# Obwod_sterowania_MOSFET.net
KiCad netlist of a schematic drawn in Altium Designer
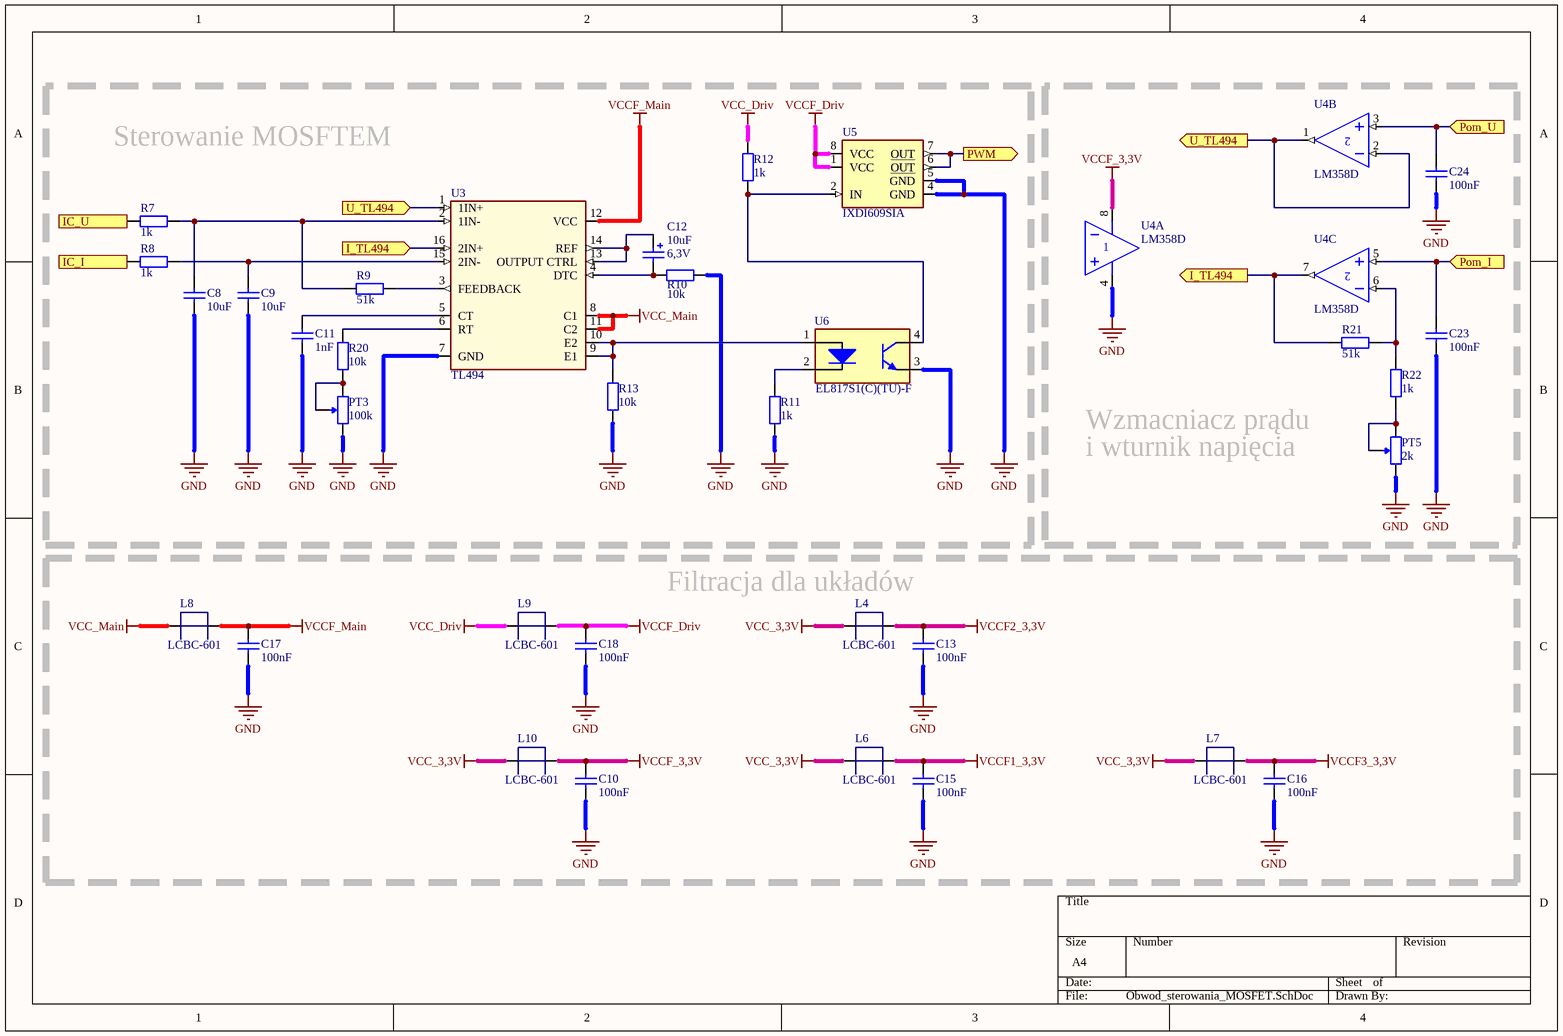
[diagram p0: Obwod_sterowania_MOSFET.SchDoc]

(export (version "E")
  (design (tool "Eeschema 10.0.6"))
  (components
    (comp (ref "C8")
      (value "Kondesator")
      (footprint "SMD-1206C")
      (fields (field (name "PARAMETR_1") "10uF"))
      (libsource (lib "MyLibrary") (part "Kondesator"))
    )
    (comp (ref "C9")
      (value "Kondesator")
      (footprint "SMD-1206C")
      (fields (field (name "PARAMETR_1") "10uF"))
      (libsource (lib "MyLibrary") (part "Kondesator"))
    )
    (comp (ref "C10")
      (value "Kondesator")
      (footprint "SMD-1206C")
      (fields (field (name "PARAMETR_1") "100nF"))
      (libsource (lib "MyLibrary") (part "Kondesator"))
    )
    (comp (ref "C11")
      (value "Kondesator")
      (footprint "SMD-1206C")
      (fields (field (name "PARAMETR_1") "1nF"))
      (libsource (lib "MyLibrary") (part "Kondesator"))
    )
    (comp (ref "C12")
      (value "Kondesator elektrolityczny")
      (footprint "SMD-1206C")
      (fields (field (name "PARAMETR_1") "10uF") (field (name "PARAMETR_2") "6,3V"))
      (libsource (lib "MyLibrary") (part "Kondesator elektrolityczny"))
    )
    (comp (ref "C13")
      (value "Kondesator")
      (footprint "SMD-1206C")
      (fields (field (name "PARAMETR_1") "100nF"))
      (libsource (lib "MyLibrary") (part "Kondesator"))
    )
    (comp (ref "C15")
      (value "Kondesator")
      (footprint "SMD-1206C")
      (fields (field (name "PARAMETR_1") "100nF"))
      (libsource (lib "MyLibrary") (part "Kondesator"))
    )
    (comp (ref "C16")
      (value "Kondesator")
      (footprint "SMD-1206C")
      (fields (field (name "PARAMETR_1") "100nF"))
      (libsource (lib "MyLibrary") (part "Kondesator"))
    )
    (comp (ref "C17")
      (value "Kondesator")
      (footprint "SMD-1206C")
      (fields (field (name "PARAMETR_1") "100nF"))
      (libsource (lib "MyLibrary") (part "Kondesator"))
    )
    (comp (ref "C18")
      (value "Kondesator")
      (footprint "SMD-1206C")
      (fields (field (name "PARAMETR_1") "100nF"))
      (libsource (lib "MyLibrary") (part "Kondesator"))
    )
    (comp (ref "C23")
      (value "Kondesator")
      (footprint "SMD-1206C")
      (fields (field (name "PARAMETR_1") "100nF"))
      (libsource (lib "MyLibrary") (part "Kondesator"))
    )
    (comp (ref "C24")
      (value "Kondesator")
      (footprint "SMD-1206C")
      (fields (field (name "PARAMETR_1") "100nF"))
      (libsource (lib "MyLibrary") (part "Kondesator"))
    )
    (comp (ref "L4")
      (value "~")
      (footprint "SMD-1206-RES")
      (fields (field (name "OZNACZENIE") "LCBC-601"))
      (libsource (lib "MyLibrary") (part "Filtr"))
    )
    (comp (ref "L6")
      (value "~")
      (footprint "SMD-1206-RES")
      (fields (field (name "OZNACZENIE") "LCBC-601"))
      (libsource (lib "MyLibrary") (part "Filtr"))
    )
    (comp (ref "L7")
      (value "~")
      (footprint "SMD-1206-RES")
      (fields (field (name "OZNACZENIE") "LCBC-601"))
      (libsource (lib "MyLibrary") (part "Filtr"))
    )
    (comp (ref "L8")
      (value "~")
      (footprint "SMD-1206-RES")
      (fields (field (name "OZNACZENIE") "LCBC-601"))
      (libsource (lib "MyLibrary") (part "Filtr"))
    )
    (comp (ref "L9")
      (value "~")
      (footprint "SMD-1206-RES")
      (fields (field (name "OZNACZENIE") "LCBC-601"))
      (libsource (lib "MyLibrary") (part "Filtr"))
    )
    (comp (ref "L10")
      (value "~")
      (footprint "SMD-1206-RES")
      (fields (field (name "OZNACZENIE") "LCBC-601"))
      (libsource (lib "MyLibrary") (part "Filtr"))
    )
    (comp (ref "PT3")
      (value "Potentiometer")
      (footprint "Potecjomert")
      (description "Potentiometer montażowy wielobortowy")
      (fields (field (name "PARAMETR_1") "100k"))
      (libsource (lib "MyLibrary") (part "Potentiometer"))
    )
    (comp (ref "PT5")
      (value "Potentiometer")
      (footprint "Potecjomert")
      (description "Potentiometer montażowy wielobortowy")
      (fields (field (name "PARAMETR_1") "2k"))
      (libsource (lib "MyLibrary") (part "Potentiometer"))
    )
    (comp (ref "R7")
      (value "Rezystor")
      (footprint "SMD-1206-RES")
      (fields (field (name "PARAMETR_1") "1k"))
      (libsource (lib "MyLibrary") (part "Rezystor"))
    )
    (comp (ref "R8")
      (value "Rezystor")
      (footprint "SMD-1206-RES")
      (fields (field (name "PARAMETR_1") "1k"))
      (libsource (lib "MyLibrary") (part "Rezystor"))
    )
    (comp (ref "R9")
      (value "Rezystor")
      (footprint "SMD-1206-RES")
      (fields (field (name "PARAMETR_1") "51k"))
      (libsource (lib "") (part "Rezystor_2"))
    )
    (comp (ref "R10")
      (value "Rezystor")
      (footprint "SMD-1206-RES")
      (fields (field (name "PARAMETR_1") "10k"))
      (libsource (lib "MyLibrary") (part "Rezystor"))
    )
    (comp (ref "R11")
      (value "Rezystor")
      (footprint "SMD-1206-RES")
      (fields (field (name "PARAMETR_1") "1k"))
      (libsource (lib "") (part "Rezystor_1"))
    )
    (comp (ref "R12")
      (value "Rezystor")
      (footprint "SMD-1206-RES")
      (fields (field (name "PARAMETR_1") "1k"))
      (libsource (lib "") (part "Rezystor_1"))
    )
    (comp (ref "R13")
      (value "Rezystor")
      (footprint "SMD-1206-RES")
      (fields (field (name "PARAMETR_1") "10k"))
      (libsource (lib "") (part "Rezystor_1"))
    )
    (comp (ref "R20")
      (value "Rezystor")
      (footprint "SMD-1206-RES")
      (fields (field (name "PARAMETR_1") "10k"))
      (libsource (lib "") (part "Rezystor_3"))
    )
    (comp (ref "R21")
      (value "Rezystor")
      (footprint "SMD-1206-RES")
      (fields (field (name "PARAMETR_1") "51k"))
      (libsource (lib "") (part "Rezystor_2"))
    )
    (comp (ref "R22")
      (value "Rezystor")
      (footprint "SMD-1206-RES")
      (fields (field (name "PARAMETR_1") "1k"))
      (libsource (lib "") (part "Rezystor_3"))
    )
    (comp (ref "U3")
      (value "TL494")
      (footprint "SOP16")
      (description "DC/DC switcher, kontroler PWM")
      (fields (field (name "OZNACZENIE") "TL494"))
      (libsource (lib "MyLibrary") (part "TL494"))
    )
    (comp (ref "U4")
      (value "LM358D")
      (footprint "SOIC8")
      (description "Wzmacniacz operacyjny")
      (fields (field (name "OZNACZENIE") "LM358D"))
      (libsource (lib "MyLibrary") (part "LM358D"))
    )
    (comp (ref "U5")
      (value "IXDI609SIA")
      (footprint "SO8")
      (description "driver MOSFET")
      (fields (field (name "OZNACZENIE") "IXDI609SIA"))
      (libsource (lib "MyLibrary") (part "IXDI609SIA"))
    )
    (comp (ref "U6")
      (value "Transoptor")
      (footprint "S1")
      (description "Kondesator elektrolityczny")
      (fields (field (name "OZNACZENIE") "EL817S1(C)(TU)-F"))
      (libsource (lib "MyLibrary") (part "EL817S1(C)(TU)-F"))
    )
  )
  (nets
    (net (code "1") (name "/IC_I") (class "Default")
      (node (ref "R8") (pin "1") (pinfunction "1_1") (pintype "passive"))
    )
    (net (code "2") (name "/IC_U") (class "Default")
      (node (ref "R7") (pin "1") (pinfunction "1_1") (pintype "passive"))
    )
    (net (code "3") (name "/I_TL494") (class "Default")
      (node (ref "R21") (pin "2") (pinfunction "2_2") (pintype "passive"))
      (node (ref "U3") (pin "16") (pinfunction "2IN+_16") (pintype "input"))
      (node (ref "U4") (pin "7") (pinfunction "OUT_7") (pintype "output"))
    )
    (net (code "4") (name "/PWM") (class "Default")
      (node (ref "U5") (pin "6") (pinfunction "OUT_6") (pintype "output"))
      (node (ref "U5") (pin "7") (pinfunction "OUT_7") (pintype "output"))
    )
    (net (code "5") (name "/Pom_I") (class "Default")
      (node (ref "C23") (pin "2") (pinfunction "2_2") (pintype "passive"))
      (node (ref "U4") (pin "5") (pinfunction "IN+_5") (pintype "input"))
    )
    (net (code "6") (name "/Pom_U") (class "Default")
      (node (ref "C24") (pin "2") (pinfunction "2_2") (pintype "passive"))
      (node (ref "U4") (pin "3") (pinfunction "IN+_3") (pintype "input"))
    )
    (net (code "7") (name "/U_TL494") (class "Default")
      (node (ref "U3") (pin "1") (pinfunction "1IN+_1") (pintype "input"))
      (node (ref "U4") (pin "1") (pinfunction "OUT_1") (pintype "output"))
      (node (ref "U4") (pin "2") (pinfunction "IN-_2") (pintype "input"))
    )
    (net (code "8") (name "GND") (class "Default")
      (node (ref "C10") (pin "1") (pinfunction "1_1") (pintype "passive"))
      (node (ref "C11") (pin "1") (pinfunction "1_1") (pintype "passive"))
      (node (ref "C13") (pin "1") (pinfunction "1_1") (pintype "passive"))
      (node (ref "C15") (pin "1") (pinfunction "1_1") (pintype "passive"))
      (node (ref "C16") (pin "1") (pinfunction "1_1") (pintype "passive"))
      (node (ref "C17") (pin "1") (pinfunction "1_1") (pintype "passive"))
      (node (ref "C18") (pin "1") (pinfunction "1_1") (pintype "passive"))
      (node (ref "C23") (pin "1") (pinfunction "1_1") (pintype "passive"))
      (node (ref "C24") (pin "1") (pinfunction "1_1") (pintype "passive"))
      (node (ref "C8") (pin "1") (pinfunction "1_1") (pintype "passive"))
      (node (ref "C9") (pin "1") (pinfunction "1_1") (pintype "passive"))
      (node (ref "PT3") (pin "3") (pinfunction "BOT_3") (pintype "passive"))
      (node (ref "PT5") (pin "3") (pinfunction "BOT_3") (pintype "passive"))
      (node (ref "R10") (pin "2") (pinfunction "2_2") (pintype "passive"))
      (node (ref "R11") (pin "1") (pinfunction "1_1") (pintype "passive"))
      (node (ref "R13") (pin "1") (pinfunction "1_1") (pintype "passive"))
      (node (ref "U3") (pin "7") (pinfunction "GND_7") (pintype "power_in"))
      (node (ref "U4") (pin "4") (pinfunction "V-_4") (pintype "power_in"))
      (node (ref "U5") (pin "4") (pinfunction "GND_4") (pintype "power_in"))
      (node (ref "U5") (pin "5") (pinfunction "GND_5") (pintype "power_in"))
      (node (ref "U6") (pin "3") (pintype "passive"))
    )
    (net (code "9") (name "Net-(PT3-TAP)") (class "Default")
      (node (ref "PT3") (pin "1") (pinfunction "TOP_1") (pintype "passive"))
      (node (ref "PT3") (pin "2") (pinfunction "TAP_2") (pintype "passive"))
      (node (ref "R20") (pin "2") (pinfunction "2_2") (pintype "passive"))
    )
    (net (code "10") (name "Net-(PT5-TAP)") (class "Default")
      (node (ref "PT5") (pin "1") (pinfunction "TOP_1") (pintype "passive"))
      (node (ref "PT5") (pin "2") (pinfunction "TAP_2") (pintype "passive"))
      (node (ref "R22") (pin "2") (pinfunction "2_2") (pintype "passive"))
    )
    (net (code "11") (name "Net-(R11-Pad2)") (class "Default")
      (node (ref "R11") (pin "2") (pinfunction "2_2") (pintype "passive"))
      (node (ref "U6") (pin "2") (pintype "passive"))
    )
    (net (code "12") (name "Net-(U3-1IN-)") (class "Default")
      (node (ref "C8") (pin "2") (pinfunction "2_2") (pintype "passive"))
      (node (ref "R7") (pin "2") (pinfunction "2_2") (pintype "passive"))
      (node (ref "R9") (pin "2") (pinfunction "2_2") (pintype "passive"))
      (node (ref "U3") (pin "2") (pinfunction "1IN-_2") (pintype "input"))
    )
    (net (code "13") (name "Net-(U3-2IN-)") (class "Default")
      (node (ref "C9") (pin "2") (pinfunction "2_2") (pintype "passive"))
      (node (ref "R8") (pin "2") (pinfunction "2_2") (pintype "passive"))
      (node (ref "U3") (pin "15") (pinfunction "2IN-_15") (pintype "input"))
    )
    (net (code "14") (name "Net-(U3-CT)") (class "Default")
      (node (ref "C11") (pin "2") (pinfunction "2_2") (pintype "passive"))
      (node (ref "U3") (pin "5") (pinfunction "CT_5") (pintype "passive"))
    )
    (net (code "15") (name "Net-(U3-DTC)") (class "Default")
      (node (ref "C12") (pin "1") (pinfunction "1_1") (pintype "passive"))
      (node (ref "R10") (pin "1") (pinfunction "1_1") (pintype "passive"))
      (node (ref "U3") (pin "4") (pinfunction "DTC_4") (pintype "input"))
    )
    (net (code "16") (name "Net-(U3-E1)") (class "Default")
      (node (ref "R13") (pin "2") (pinfunction "2_2") (pintype "passive"))
      (node (ref "U3") (pin "10") (pinfunction "E2_10") (pintype "passive"))
      (node (ref "U3") (pin "9") (pinfunction "E1_9") (pintype "passive"))
      (node (ref "U6") (pin "1") (pintype "passive"))
    )
    (net (code "17") (name "Net-(U3-FEEDBACK)") (class "Default")
      (node (ref "R9") (pin "1") (pinfunction "1_1") (pintype "passive"))
      (node (ref "U3") (pin "3") (pinfunction "FEEDBACK_3") (pintype "output"))
    )
    (net (code "18") (name "Net-(U3-OUTPUT_CTRL)") (class "Default")
      (node (ref "C12") (pin "2") (pinfunction "2_2") (pintype "passive"))
      (node (ref "U3") (pin "13") (pinfunction "OUTPUT_CTRL_13") (pintype "input"))
      (node (ref "U3") (pin "14") (pinfunction "REF_14") (pintype "output"))
    )
    (net (code "19") (name "Net-(U3-RT)") (class "Default")
      (node (ref "R20") (pin "1") (pinfunction "1_1") (pintype "passive"))
      (node (ref "U3") (pin "6") (pinfunction "RT_6") (pintype "passive"))
    )
    (net (code "20") (name "Net-(U4C-IN-)") (class "Default")
      (node (ref "R21") (pin "1") (pinfunction "1_1") (pintype "passive"))
      (node (ref "R22") (pin "1") (pinfunction "1_1") (pintype "passive"))
      (node (ref "U4") (pin "6") (pinfunction "IN-_6") (pintype "input"))
    )
    (net (code "21") (name "Net-(U5-IN)") (class "Default")
      (node (ref "R12") (pin "1") (pinfunction "1_1") (pintype "passive"))
      (node (ref "U5") (pin "2") (pinfunction "IN_2") (pintype "input"))
      (node (ref "U6") (pin "4") (pintype "passive"))
    )
    (net (code "22") (name "VCCF1_3,3V") (class "Default")
      (node (ref "C15") (pin "2") (pinfunction "2_2") (pintype "passive"))
      (node (ref "L6") (pin "2") (pintype "passive"))
    )
    (net (code "23") (name "VCCF2_3,3V") (class "Default")
      (node (ref "C13") (pin "2") (pinfunction "2_2") (pintype "passive"))
      (node (ref "L4") (pin "2") (pintype "passive"))
    )
    (net (code "24") (name "VCCF3_3,3V") (class "Default")
      (node (ref "C16") (pin "2") (pinfunction "2_2") (pintype "passive"))
      (node (ref "L7") (pin "2") (pintype "passive"))
    )
    (net (code "25") (name "VCCF_3,3V") (class "Default")
      (node (ref "C10") (pin "2") (pinfunction "2_2") (pintype "passive"))
      (node (ref "L10") (pin "2") (pintype "passive"))
      (node (ref "U4") (pin "8") (pinfunction "V+_8") (pintype "power_in"))
    )
    (net (code "26") (name "VCCF_Driv") (class "Default")
      (node (ref "C18") (pin "2") (pinfunction "2_2") (pintype "passive"))
      (node (ref "L9") (pin "2") (pintype "passive"))
      (node (ref "U5") (pin "1") (pinfunction "VCC_1") (pintype "power_in"))
      (node (ref "U5") (pin "8") (pinfunction "VCC_8") (pintype "power_in"))
    )
    (net (code "27") (name "VCCF_Main") (class "Default")
      (node (ref "C17") (pin "2") (pinfunction "2_2") (pintype "passive"))
      (node (ref "L8") (pin "2") (pintype "passive"))
      (node (ref "U3") (pin "12") (pinfunction "VCC_12") (pintype "power_in"))
    )
    (net (code "28") (name "VCC_3,3V") (class "Default")
      (node (ref "L10") (pin "1") (pintype "passive"))
      (node (ref "L4") (pin "1") (pintype "passive"))
      (node (ref "L6") (pin "1") (pintype "passive"))
      (node (ref "L7") (pin "1") (pintype "passive"))
    )
    (net (code "29") (name "VCC_Driv") (class "Default")
      (node (ref "L9") (pin "1") (pintype "passive"))
      (node (ref "R12") (pin "2") (pinfunction "2_2") (pintype "passive"))
    )
    (net (code "30") (name "VCC_Main") (class "Default")
      (node (ref "L8") (pin "1") (pintype "passive"))
      (node (ref "U3") (pin "11") (pinfunction "C2_11") (pintype "passive"))
      (node (ref "U3") (pin "8") (pinfunction "C1_8") (pintype "passive"))
    )
  )
)
